# Relay_Charge_Circuit.net
KiCad netlist of a schematic drawn in EAGLE
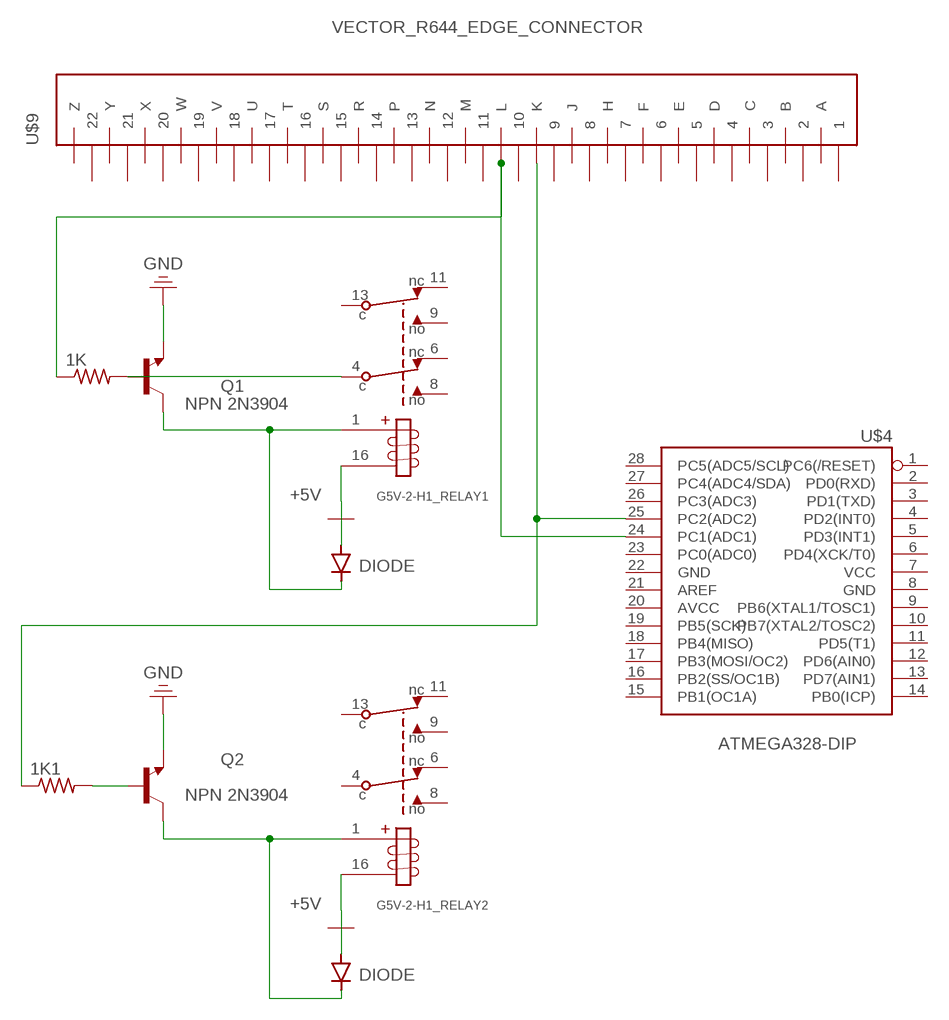
[diagram p0: schematic, sheet 1]

(export (version "E")
  (design (tool "Eeschema 10.0.6"))
  (components
    (comp (ref "1K")
      (value "R-US_0414/5V")
      (footprint "eagle-import:0414V")
      (libsource (lib "eagle-import") (part "R-US_0414/5V"))
    )
    (comp (ref "1K1")
      (value "R-US_0414/5V")
      (footprint "eagle-import:0414V")
      (libsource (lib "eagle-import") (part "R-US_0414/5V"))
    )
    (comp (ref "G5V-2-H1_RELAY1")
      (value "RELAY_DPDT")
      (footprint "eagle-import:DIP16_RELAY")
      (libsource (lib "eagle-import") (part "RELAY_DPDT"))
    )
    (comp (ref "G5V-2-H1_RELAY2")
      (value "RELAY_DPDT")
      (footprint "eagle-import:DIP16_RELAY")
      (libsource (lib "eagle-import") (part "RELAY_DPDT"))
    )
    (comp (ref "Q1")
      (value "NPN 2N3904")
      (footprint "eagle-import:TO92")
      (libsource (lib "eagle-import") (part "NPN_TO92_"))
    )
    (comp (ref "Q2")
      (value "NPN 2N3904")
      (footprint "eagle-import:TO92")
      (libsource (lib "eagle-import") (part "NPN_TO92_"))
    )
    (comp (ref "U$3")
      (value "DIODE")
      (footprint "eagle-import:DIODE-DO-220AA(SMP)")
      (libsource (lib "eagle-import") (part "DIODE"))
    )
    (comp (ref "U$4")
      (value "ATMEGA328-DIP")
      (footprint "eagle-import:DIP28")
      (libsource (lib "eagle-import") (part "ATMEGA328-DIP"))
    )
    (comp (ref "U$6")
      (value "DIODE")
      (footprint "eagle-import:DIODE-DO-220AA(SMP)")
      (libsource (lib "eagle-import") (part "DIODE"))
    )
    (comp (ref "U$9")
      (value "VECTOR_R644_EDGE_CONNECTOR")
      (footprint "eagle-import:VECTOR44")
      (libsource (lib "eagle-import") (part "VECTOR_R644_EDGE_CONNECTOR"))
    )
  )
  (nets
    (net (code "1") (name "+5V") (class "Default")
      (node (ref "G5V-2-H1_RELAY1") (pin "16") (pinfunction "P$16_16") (pintype "input"))
      (node (ref "G5V-2-H1_RELAY2") (pin "16") (pinfunction "P$16_16") (pintype "input"))
      (node (ref "U$3") (pin "ANODE") (pinfunction "ANODE_ANODE") (pintype "bidirectional"))
      (node (ref "U$6") (pin "ANODE") (pinfunction "ANODE_ANODE") (pintype "bidirectional"))
    )
    (net (code "2") (name "GND") (class "Default")
      (node (ref "Q1") (pin "3") (pinfunction "E_3") (pintype "passive"))
      (node (ref "Q2") (pin "3") (pinfunction "E_3") (pintype "passive"))
    )
    (net (code "3") (name "Net-(G5V-2-H1_RELAY1-P$1)") (class "Default")
      (node (ref "G5V-2-H1_RELAY1") (pin "1") (pinfunction "P$1_1") (pintype "input"))
      (node (ref "Q1") (pin "1") (pinfunction "C_1") (pintype "passive"))
      (node (ref "U$3") (pin "CATHODE") (pinfunction "CATHODE_CATHODE") (pintype "bidirectional"))
    )
    (net (code "4") (name "Net-(G5V-2-H1_RELAY1-P$4)") (class "Default")
      (node (ref "1K") (pin "2") (pinfunction "2_2") (pintype "passive"))
      (node (ref "G5V-2-H1_RELAY1") (pin "P1") (pinfunction "P$4_P1") (pintype "bidirectional"))
      (node (ref "Q1") (pin "2") (pinfunction "B_2") (pintype "passive"))
    )
    (net (code "5") (name "Net-(G5V-2-H1_RELAY2-P$1)") (class "Default")
      (node (ref "G5V-2-H1_RELAY2") (pin "1") (pinfunction "P$1_1") (pintype "input"))
      (node (ref "Q2") (pin "1") (pinfunction "C_1") (pintype "passive"))
      (node (ref "U$6") (pin "CATHODE") (pinfunction "CATHODE_CATHODE") (pintype "bidirectional"))
    )
    (net (code "6") (name "Net-(Q2-B)") (class "Default")
      (node (ref "1K1") (pin "2") (pinfunction "2_2") (pintype "passive"))
      (node (ref "Q2") (pin "2") (pinfunction "B_2") (pintype "passive"))
    )
    (net (code "7") (name "Net-(U$4-PC1(ADC1))") (class "Default")
      (node (ref "1K") (pin "1") (pinfunction "1_1") (pintype "passive"))
      (node (ref "U$4") (pin "24") (pinfunction "PC1(ADC1)_24") (pintype "bidirectional"))
      (node (ref "U$9") (pin "P$L") (pinfunction "L_P$L") (pintype "bidirectional"))
    )
    (net (code "8") (name "Net-(U$4-PC2(ADC2))") (class "Default")
      (node (ref "1K1") (pin "1") (pinfunction "1_1") (pintype "passive"))
      (node (ref "U$4") (pin "25") (pinfunction "PC2(ADC2)_25") (pintype "bidirectional"))
      (node (ref "U$9") (pin "P$K") (pinfunction "K_P$K") (pintype "bidirectional"))
    )
    (net (code "9") (name "unconnected-(G5V-2-H1_RELAY1-P$6-PadO1)") (class "Default")
      (node (ref "G5V-2-H1_RELAY1") (pin "O1") (pinfunction "P$6_O1") (pintype "bidirectional"))
    )
    (net (code "10") (name "unconnected-(G5V-2-H1_RELAY1-P$8-PadS1)") (class "Default")
      (node (ref "G5V-2-H1_RELAY1") (pin "S1") (pinfunction "P$8_S1") (pintype "bidirectional"))
    )
    (net (code "11") (name "unconnected-(G5V-2-H1_RELAY1-P$9-PadS2)") (class "Default")
      (node (ref "G5V-2-H1_RELAY1") (pin "S2") (pinfunction "P$9_S2") (pintype "bidirectional"))
    )
    (net (code "12") (name "unconnected-(G5V-2-H1_RELAY1-P$11-PadO2)") (class "Default")
      (node (ref "G5V-2-H1_RELAY1") (pin "O2") (pinfunction "P$11_O2") (pintype "bidirectional"))
    )
    (net (code "13") (name "unconnected-(G5V-2-H1_RELAY1-P$13-PadP2)") (class "Default")
      (node (ref "G5V-2-H1_RELAY1") (pin "P2") (pinfunction "P$13_P2") (pintype "bidirectional"))
    )
    (net (code "14") (name "unconnected-(G5V-2-H1_RELAY2-P$4-PadP1)") (class "Default")
      (node (ref "G5V-2-H1_RELAY2") (pin "P1") (pinfunction "P$4_P1") (pintype "bidirectional"))
    )
    (net (code "15") (name "unconnected-(G5V-2-H1_RELAY2-P$6-PadO1)") (class "Default")
      (node (ref "G5V-2-H1_RELAY2") (pin "O1") (pinfunction "P$6_O1") (pintype "bidirectional"))
    )
    (net (code "16") (name "unconnected-(G5V-2-H1_RELAY2-P$8-PadS1)") (class "Default")
      (node (ref "G5V-2-H1_RELAY2") (pin "S1") (pinfunction "P$8_S1") (pintype "bidirectional"))
    )
    (net (code "17") (name "unconnected-(G5V-2-H1_RELAY2-P$9-PadS2)") (class "Default")
      (node (ref "G5V-2-H1_RELAY2") (pin "S2") (pinfunction "P$9_S2") (pintype "bidirectional"))
    )
    (net (code "18") (name "unconnected-(G5V-2-H1_RELAY2-P$11-PadO2)") (class "Default")
      (node (ref "G5V-2-H1_RELAY2") (pin "O2") (pinfunction "P$11_O2") (pintype "bidirectional"))
    )
    (net (code "19") (name "unconnected-(G5V-2-H1_RELAY2-P$13-PadP2)") (class "Default")
      (node (ref "G5V-2-H1_RELAY2") (pin "P2") (pinfunction "P$13_P2") (pintype "bidirectional"))
    )
    (net (code "20") (name "unconnected-(U$4-AREF-Pad21)") (class "Default")
      (node (ref "U$4") (pin "21") (pinfunction "AREF_21") (pintype "bidirectional"))
    )
    (net (code "21") (name "unconnected-(U$4-AVCC-Pad20)") (class "Default")
      (node (ref "U$4") (pin "20") (pinfunction "AVCC_20") (pintype "bidirectional"))
    )
    (net (code "22") (name "unconnected-(U$4-GND-Pad8)") (class "Default")
      (node (ref "U$4") (pin "8") (pinfunction "GND_8") (pintype "bidirectional"))
    )
    (net (code "23") (name "unconnected-(U$4-GND-Pad22)") (class "Default")
      (node (ref "U$4") (pin "22") (pinfunction "GND_22") (pintype "bidirectional"))
    )
    (net (code "24") (name "unconnected-(U$4-PB0(ICP)-Pad14)") (class "Default")
      (node (ref "U$4") (pin "14") (pinfunction "PB0(ICP)_14") (pintype "bidirectional"))
    )
    (net (code "25") (name "unconnected-(U$4-PB1(OC1A)-Pad15)") (class "Default")
      (node (ref "U$4") (pin "15") (pinfunction "PB1(OC1A)_15") (pintype "bidirectional"))
    )
    (net (code "26") (name "unconnected-(U$4-PB2(SS{slash}OC1B)-Pad16)") (class "Default")
      (node (ref "U$4") (pin "16") (pinfunction "PB2(SS/OC1B)_16") (pintype "bidirectional"))
    )
    (net (code "27") (name "unconnected-(U$4-PB3(MOSI{slash}OC2)-Pad17)") (class "Default")
      (node (ref "U$4") (pin "17") (pinfunction "PB3(MOSI/OC2)_17") (pintype "bidirectional"))
    )
    (net (code "28") (name "unconnected-(U$4-PB4(MISO)-Pad18)") (class "Default")
      (node (ref "U$4") (pin "18") (pinfunction "PB4(MISO)_18") (pintype "bidirectional"))
    )
    (net (code "29") (name "unconnected-(U$4-PB5(SCK)-Pad19)") (class "Default")
      (node (ref "U$4") (pin "19") (pinfunction "PB5(SCK)_19") (pintype "bidirectional"))
    )
    (net (code "30") (name "unconnected-(U$4-PB6(XTAL1{slash}TOSC1)-Pad9)") (class "Default")
      (node (ref "U$4") (pin "9") (pinfunction "PB6(XTAL1/TOSC1)_9") (pintype "bidirectional"))
    )
    (net (code "31") (name "unconnected-(U$4-PB7(XTAL2{slash}TOSC2)-Pad10)") (class "Default")
      (node (ref "U$4") (pin "10") (pinfunction "PB7(XTAL2/TOSC2)_10") (pintype "bidirectional"))
    )
    (net (code "32") (name "unconnected-(U$4-PC0(ADC0)-Pad23)") (class "Default")
      (node (ref "U$4") (pin "23") (pinfunction "PC0(ADC0)_23") (pintype "bidirectional"))
    )
    (net (code "33") (name "unconnected-(U$4-PC3(ADC3)-Pad26)") (class "Default")
      (node (ref "U$4") (pin "26") (pinfunction "PC3(ADC3)_26") (pintype "bidirectional"))
    )
    (net (code "34") (name "unconnected-(U$4-PC4(ADC4{slash}SDA)-Pad27)") (class "Default")
      (node (ref "U$4") (pin "27") (pinfunction "PC4(ADC4/SDA)_27") (pintype "bidirectional"))
    )
    (net (code "35") (name "unconnected-(U$4-PC5(ADC5{slash}SCL)-Pad28)") (class "Default")
      (node (ref "U$4") (pin "28") (pinfunction "PC5(ADC5/SCL)_28") (pintype "bidirectional"))
    )
    (net (code "36") (name "unconnected-(U$4-PC6({slash}RESET)-Pad1)") (class "Default")
      (node (ref "U$4") (pin "1") (pinfunction "PC6(/RESET)_1") (pintype "bidirectional"))
    )
    (net (code "37") (name "unconnected-(U$4-PD0(RXD)-Pad2)") (class "Default")
      (node (ref "U$4") (pin "2") (pinfunction "PD0(RXD)_2") (pintype "bidirectional"))
    )
    (net (code "38") (name "unconnected-(U$4-PD1(TXD)-Pad3)") (class "Default")
      (node (ref "U$4") (pin "3") (pinfunction "PD1(TXD)_3") (pintype "bidirectional"))
    )
    (net (code "39") (name "unconnected-(U$4-PD2(INT0)-Pad4)") (class "Default")
      (node (ref "U$4") (pin "4") (pinfunction "PD2(INT0)_4") (pintype "bidirectional"))
    )
    (net (code "40") (name "unconnected-(U$4-PD3(INT1)-Pad5)") (class "Default")
      (node (ref "U$4") (pin "5") (pinfunction "PD3(INT1)_5") (pintype "bidirectional"))
    )
    (net (code "41") (name "unconnected-(U$4-PD4(XCK{slash}T0)-Pad6)") (class "Default")
      (node (ref "U$4") (pin "6") (pinfunction "PD4(XCK/T0)_6") (pintype "bidirectional"))
    )
    (net (code "42") (name "unconnected-(U$4-PD5(T1)-Pad11)") (class "Default")
      (node (ref "U$4") (pin "11") (pinfunction "PD5(T1)_11") (pintype "bidirectional"))
    )
    (net (code "43") (name "unconnected-(U$4-PD6(AIN0)-Pad12)") (class "Default")
      (node (ref "U$4") (pin "12") (pinfunction "PD6(AIN0)_12") (pintype "bidirectional"))
    )
    (net (code "44") (name "unconnected-(U$4-PD7(AIN1)-Pad13)") (class "Default")
      (node (ref "U$4") (pin "13") (pinfunction "PD7(AIN1)_13") (pintype "bidirectional"))
    )
    (net (code "45") (name "unconnected-(U$4-VCC-Pad7)") (class "Default")
      (node (ref "U$4") (pin "7") (pinfunction "VCC_7") (pintype "bidirectional"))
    )
    (net (code "46") (name "unconnected-(U$9-1-PadP$1)") (class "Default")
      (node (ref "U$9") (pin "P$1") (pinfunction "1_P$1") (pintype "bidirectional"))
    )
    (net (code "47") (name "unconnected-(U$9-2-PadP$2)") (class "Default")
      (node (ref "U$9") (pin "P$2") (pinfunction "2_P$2") (pintype "bidirectional"))
    )
    (net (code "48") (name "unconnected-(U$9-3-PadP$3)") (class "Default")
      (node (ref "U$9") (pin "P$3") (pinfunction "3_P$3") (pintype "bidirectional"))
    )
    (net (code "49") (name "unconnected-(U$9-4-PadP$4)") (class "Default")
      (node (ref "U$9") (pin "P$4") (pinfunction "4_P$4") (pintype "bidirectional"))
    )
    (net (code "50") (name "unconnected-(U$9-5-PadP$5)") (class "Default")
      (node (ref "U$9") (pin "P$5") (pinfunction "5_P$5") (pintype "bidirectional"))
    )
    (net (code "51") (name "unconnected-(U$9-6-PadP$6)") (class "Default")
      (node (ref "U$9") (pin "P$6") (pinfunction "6_P$6") (pintype "bidirectional"))
    )
    (net (code "52") (name "unconnected-(U$9-7-PadP$7)") (class "Default")
      (node (ref "U$9") (pin "P$7") (pinfunction "7_P$7") (pintype "bidirectional"))
    )
    (net (code "53") (name "unconnected-(U$9-8-PadP$8)") (class "Default")
      (node (ref "U$9") (pin "P$8") (pinfunction "8_P$8") (pintype "bidirectional"))
    )
    (net (code "54") (name "unconnected-(U$9-9-PadP$9)") (class "Default")
      (node (ref "U$9") (pin "P$9") (pinfunction "9_P$9") (pintype "bidirectional"))
    )
    (net (code "55") (name "unconnected-(U$9-10-PadP$10)") (class "Default")
      (node (ref "U$9") (pin "P$10") (pinfunction "10_P$10") (pintype "bidirectional"))
    )
    (net (code "56") (name "unconnected-(U$9-11-PadP$11)") (class "Default")
      (node (ref "U$9") (pin "P$11") (pinfunction "11_P$11") (pintype "bidirectional"))
    )
    (net (code "57") (name "unconnected-(U$9-12-PadP$12)") (class "Default")
      (node (ref "U$9") (pin "P$12") (pinfunction "12_P$12") (pintype "bidirectional"))
    )
    (net (code "58") (name "unconnected-(U$9-13-PadP$13)") (class "Default")
      (node (ref "U$9") (pin "P$13") (pinfunction "13_P$13") (pintype "bidirectional"))
    )
    (net (code "59") (name "unconnected-(U$9-14-PadP$14)") (class "Default")
      (node (ref "U$9") (pin "P$14") (pinfunction "14_P$14") (pintype "bidirectional"))
    )
    (net (code "60") (name "unconnected-(U$9-15-PadP$15)") (class "Default")
      (node (ref "U$9") (pin "P$15") (pinfunction "15_P$15") (pintype "bidirectional"))
    )
    (net (code "61") (name "unconnected-(U$9-16-PadP$16)") (class "Default")
      (node (ref "U$9") (pin "P$16") (pinfunction "16_P$16") (pintype "bidirectional"))
    )
    (net (code "62") (name "unconnected-(U$9-17-PadP$17)") (class "Default")
      (node (ref "U$9") (pin "P$17") (pinfunction "17_P$17") (pintype "bidirectional"))
    )
    (net (code "63") (name "unconnected-(U$9-18-PadP$18)") (class "Default")
      (node (ref "U$9") (pin "P$18") (pinfunction "18_P$18") (pintype "bidirectional"))
    )
    (net (code "64") (name "unconnected-(U$9-19-PadP$19)") (class "Default")
      (node (ref "U$9") (pin "P$19") (pinfunction "19_P$19") (pintype "bidirectional"))
    )
    (net (code "65") (name "unconnected-(U$9-20-PadP$20)") (class "Default")
      (node (ref "U$9") (pin "P$20") (pinfunction "20_P$20") (pintype "bidirectional"))
    )
    (net (code "66") (name "unconnected-(U$9-21-PadP$21)") (class "Default")
      (node (ref "U$9") (pin "P$21") (pinfunction "21_P$21") (pintype "bidirectional"))
    )
    (net (code "67") (name "unconnected-(U$9-22-PadP$22)") (class "Default")
      (node (ref "U$9") (pin "P$22") (pinfunction "22_P$22") (pintype "bidirectional"))
    )
    (net (code "68") (name "unconnected-(U$9-A-PadP$A)") (class "Default")
      (node (ref "U$9") (pin "P$A") (pinfunction "A_P$A") (pintype "bidirectional"))
    )
    (net (code "69") (name "unconnected-(U$9-B-PadP$B)") (class "Default")
      (node (ref "U$9") (pin "P$B") (pinfunction "B_P$B") (pintype "bidirectional"))
    )
    (net (code "70") (name "unconnected-(U$9-C-PadP$C)") (class "Default")
      (node (ref "U$9") (pin "P$C") (pinfunction "C_P$C") (pintype "bidirectional"))
    )
    (net (code "71") (name "unconnected-(U$9-D-PadP$D)") (class "Default")
      (node (ref "U$9") (pin "P$D") (pinfunction "D_P$D") (pintype "bidirectional"))
    )
    (net (code "72") (name "unconnected-(U$9-E-PadP$E)") (class "Default")
      (node (ref "U$9") (pin "P$E") (pinfunction "E_P$E") (pintype "bidirectional"))
    )
    (net (code "73") (name "unconnected-(U$9-F-PadP$F)") (class "Default")
      (node (ref "U$9") (pin "P$F") (pinfunction "F_P$F") (pintype "bidirectional"))
    )
    (net (code "74") (name "unconnected-(U$9-H-PadP$H)") (class "Default")
      (node (ref "U$9") (pin "P$H") (pinfunction "H_P$H") (pintype "bidirectional"))
    )
    (net (code "75") (name "unconnected-(U$9-J-PadP$J)") (class "Default")
      (node (ref "U$9") (pin "P$J") (pinfunction "J_P$J") (pintype "bidirectional"))
    )
    (net (code "76") (name "unconnected-(U$9-M-PadP$M)") (class "Default")
      (node (ref "U$9") (pin "P$M") (pinfunction "M_P$M") (pintype "bidirectional"))
    )
    (net (code "77") (name "unconnected-(U$9-N-PadP$N)") (class "Default")
      (node (ref "U$9") (pin "P$N") (pinfunction "N_P$N") (pintype "bidirectional"))
    )
    (net (code "78") (name "unconnected-(U$9-P-PadP$P)") (class "Default")
      (node (ref "U$9") (pin "P$P") (pinfunction "P_P$P") (pintype "bidirectional"))
    )
    (net (code "79") (name "unconnected-(U$9-R-PadP$R)") (class "Default")
      (node (ref "U$9") (pin "P$R") (pinfunction "R_P$R") (pintype "bidirectional"))
    )
    (net (code "80") (name "unconnected-(U$9-S-PadP$S)") (class "Default")
      (node (ref "U$9") (pin "P$S") (pinfunction "S_P$S") (pintype "bidirectional"))
    )
    (net (code "81") (name "unconnected-(U$9-T-PadP$T)") (class "Default")
      (node (ref "U$9") (pin "P$T") (pinfunction "T_P$T") (pintype "bidirectional"))
    )
    (net (code "82") (name "unconnected-(U$9-U-PadP$U)") (class "Default")
      (node (ref "U$9") (pin "P$U") (pinfunction "U_P$U") (pintype "bidirectional"))
    )
    (net (code "83") (name "unconnected-(U$9-V-PadP$V)") (class "Default")
      (node (ref "U$9") (pin "P$V") (pinfunction "V_P$V") (pintype "bidirectional"))
    )
    (net (code "84") (name "unconnected-(U$9-W-PadP$W)") (class "Default")
      (node (ref "U$9") (pin "P$W") (pinfunction "W_P$W") (pintype "bidirectional"))
    )
    (net (code "85") (name "unconnected-(U$9-X-PadP$X)") (class "Default")
      (node (ref "U$9") (pin "P$X") (pinfunction "X_P$X") (pintype "bidirectional"))
    )
    (net (code "86") (name "unconnected-(U$9-Y-PadP$Y)") (class "Default")
      (node (ref "U$9") (pin "P$Y") (pinfunction "Y_P$Y") (pintype "bidirectional"))
    )
    (net (code "87") (name "unconnected-(U$9-Z-PadP$Z)") (class "Default")
      (node (ref "U$9") (pin "P$Z") (pinfunction "Z_P$Z") (pintype "bidirectional"))
    )
  )
)
